# gatedriver.net
KiCad netlist of a schematic drawn in Altium Designer
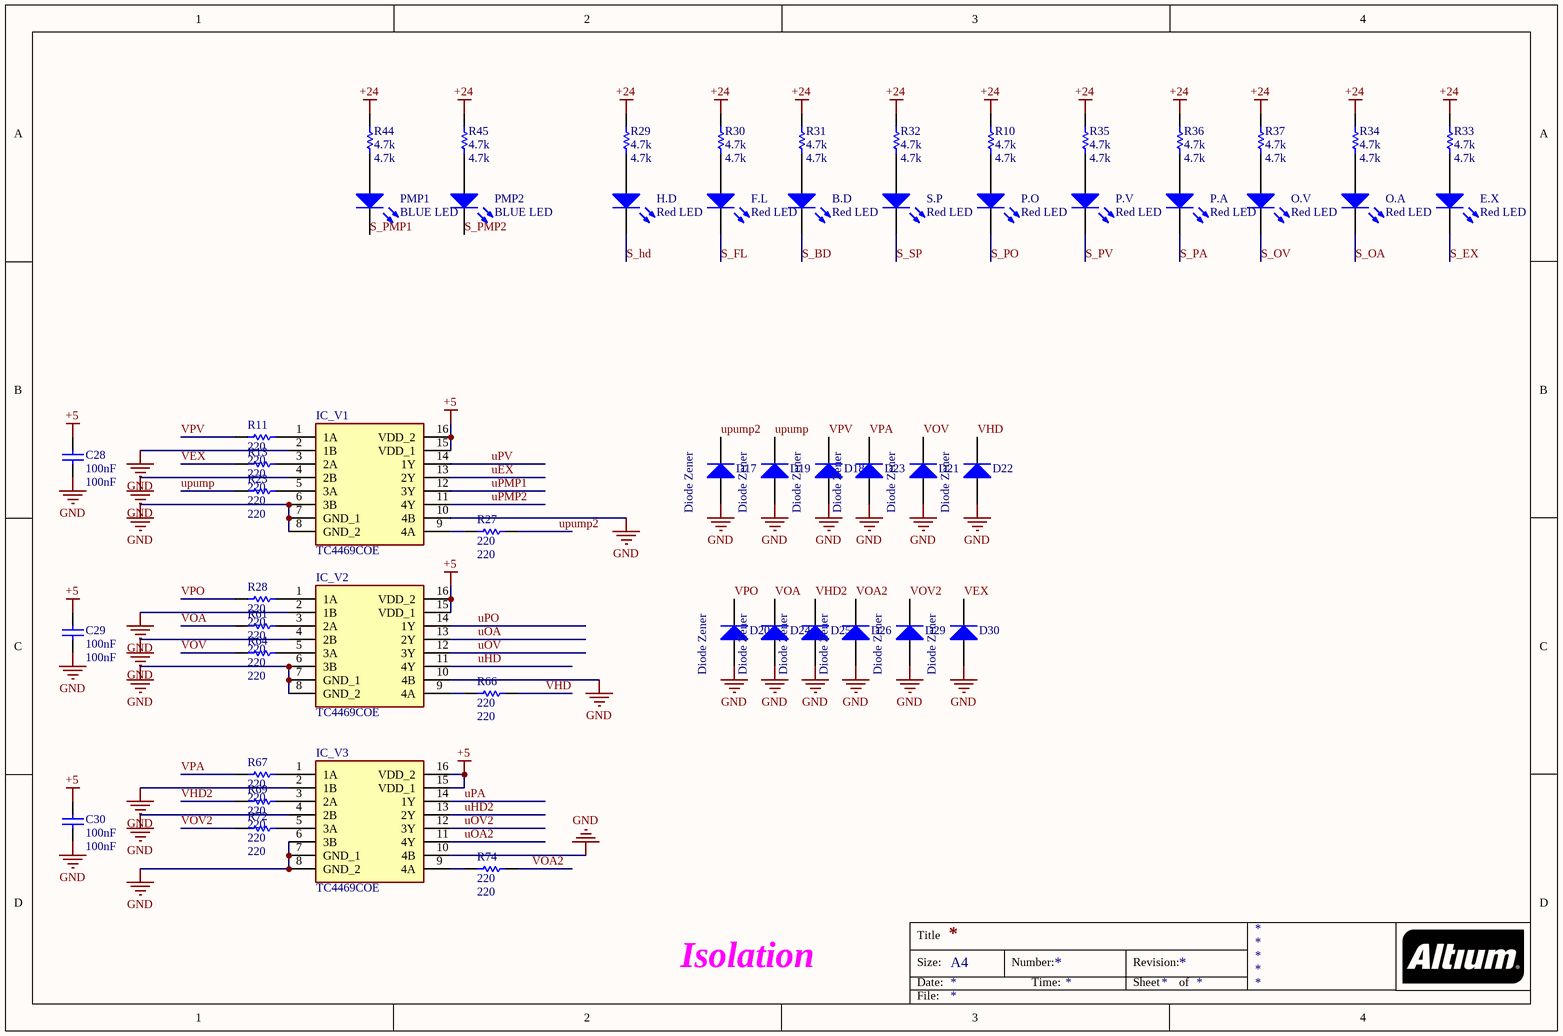
[diagram p0: gatedriver.SchDoc]

(export (version "E")
  (design (tool "Eeschema 10.0.6"))
  (components
    (comp (ref "B.D")
      (value "Red LED")
      (footprint "3518")
      (description "Typical BLUE SiC LED")
      (fields (field (name "PUBLISHER") "Altium Limited"))
      (libsource (lib "Miscellaneous Devices") (part "LED3"))
    )
    (comp (ref "C28")
      (value "100nF")
      (footprint "0805")
      (description "Capacitor")
      (fields
        (field (name "MANUFACTURER") "Generic Components")
        (field (name "ALTIUM_VALUE") "100nF")
        (field (name "PUBLISHER") "Altium Hobart Technology Centre")
      )
      (libsource (lib "Miscellaneous Devices") (part "Cap"))
    )
    (comp (ref "C29")
      (value "100nF")
      (footprint "0805")
      (description "Capacitor")
      (fields
        (field (name "MANUFACTURER") "Generic Components")
        (field (name "ALTIUM_VALUE") "100nF")
        (field (name "PUBLISHER") "Altium Hobart Technology Centre")
      )
      (libsource (lib "Miscellaneous Devices") (part "Cap"))
    )
    (comp (ref "C30")
      (value "100nF")
      (footprint "0805")
      (description "Capacitor")
      (fields
        (field (name "MANUFACTURER") "Generic Components")
        (field (name "ALTIUM_VALUE") "100nF")
        (field (name "PUBLISHER") "Altium Hobart Technology Centre")
      )
      (libsource (lib "Miscellaneous Devices") (part "Cap"))
    )
    (comp (ref "D17")
      (value "Diode Zener")
      (footprint "d1805")
      (description "High Conductance Fast Diode")
      (fields (field (name "PUBLISHER") "Altium Limited"))
      (libsource (lib "Miscellaneous Devices") (part "Diode 1N914"))
    )
    (comp (ref "D18")
      (value "Diode Zener")
      (footprint "d1805")
      (description "High Conductance Fast Diode")
      (fields (field (name "PUBLISHER") "Altium Limited"))
      (libsource (lib "Miscellaneous Devices") (part "Diode 1N914"))
    )
    (comp (ref "D19")
      (value "Diode Zener")
      (footprint "d1805")
      (description "High Conductance Fast Diode")
      (fields (field (name "PUBLISHER") "Altium Limited"))
      (libsource (lib "Miscellaneous Devices") (part "Diode 1N914"))
    )
    (comp (ref "D20")
      (value "Diode Zener")
      (footprint "d1805")
      (description "High Conductance Fast Diode")
      (fields (field (name "PUBLISHER") "Altium Limited"))
      (libsource (lib "Miscellaneous Devices") (part "Diode 1N914"))
    )
    (comp (ref "D21")
      (value "Diode Zener")
      (footprint "d1805")
      (description "High Conductance Fast Diode")
      (fields (field (name "PUBLISHER") "Altium Limited"))
      (libsource (lib "Miscellaneous Devices") (part "Diode 1N914"))
    )
    (comp (ref "D22")
      (value "Diode Zener")
      (footprint "d1805")
      (description "High Conductance Fast Diode")
      (fields (field (name "PUBLISHER") "Altium Limited"))
      (libsource (lib "Miscellaneous Devices") (part "Diode 1N914"))
    )
    (comp (ref "D23")
      (value "Diode Zener")
      (footprint "d1805")
      (description "High Conductance Fast Diode")
      (fields (field (name "PUBLISHER") "Altium Limited"))
      (libsource (lib "Miscellaneous Devices") (part "Diode 1N914"))
    )
    (comp (ref "D24")
      (value "Diode Zener")
      (footprint "d1805")
      (description "High Conductance Fast Diode")
      (fields (field (name "PUBLISHER") "Altium Limited"))
      (libsource (lib "Miscellaneous Devices") (part "Diode 1N914"))
    )
    (comp (ref "D25")
      (value "Diode Zener")
      (footprint "d1805")
      (description "High Conductance Fast Diode")
      (fields (field (name "PUBLISHER") "Altium Limited"))
      (libsource (lib "Miscellaneous Devices") (part "Diode 1N914"))
    )
    (comp (ref "D26")
      (value "Diode Zener")
      (footprint "d1805")
      (description "High Conductance Fast Diode")
      (fields (field (name "PUBLISHER") "Altium Limited"))
      (libsource (lib "Miscellaneous Devices") (part "Diode 1N914"))
    )
    (comp (ref "D29")
      (value "Diode Zener")
      (footprint "d1805")
      (description "High Conductance Fast Diode")
      (fields (field (name "PUBLISHER") "Altium Limited"))
      (libsource (lib "Miscellaneous Devices") (part "Diode 1N914"))
    )
    (comp (ref "D30")
      (value "Diode Zener")
      (footprint "d1805")
      (description "High Conductance Fast Diode")
      (fields (field (name "PUBLISHER") "Altium Limited"))
      (libsource (lib "Miscellaneous Devices") (part "Diode 1N914"))
    )
    (comp (ref "E.X")
      (value "Red LED")
      (footprint "3518")
      (description "Typical BLUE SiC LED")
      (fields (field (name "PUBLISHER") "Altium Limited"))
      (libsource (lib "Miscellaneous Devices") (part "LED3"))
    )
    (comp (ref "F.L")
      (value "Red LED")
      (footprint "3518")
      (description "Typical BLUE SiC LED")
      (fields (field (name "PUBLISHER") "Altium Limited"))
      (libsource (lib "Miscellaneous Devices") (part "LED3"))
    )
    (comp (ref "H.D")
      (value "Red LED")
      (footprint "3518")
      (description "Typical BLUE SiC LED")
      (fields (field (name "PUBLISHER") "Altium Limited"))
      (libsource (lib "Miscellaneous Devices") (part "LED3"))
    )
    (comp (ref "IC_V1")
      (value "TC4469COE")
      (footprint "SamacSys:SOIC127P1034X264-16N")
      (description "Integrated Circuit")
      (fields (field (name "MOUSER PART NUMBER") "579-TC4469COE"))
      (libsource (lib "*") (part "TC4469COE"))
    )
    (comp (ref "IC_V2")
      (value "TC4469COE")
      (footprint "SamacSys:SOIC127P1034X264-16N")
      (description "Integrated Circuit")
      (fields (field (name "MOUSER PART NUMBER") "579-TC4469COE"))
      (libsource (lib "*") (part "TC4469COE"))
    )
    (comp (ref "IC_V3")
      (value "TC4469COE")
      (footprint "SamacSys:SOIC127P1034X264-16N")
      (description "Integrated Circuit")
      (fields (field (name "MOUSER PART NUMBER") "579-TC4469COE"))
      (libsource (lib "*") (part "TC4469COE"))
    )
    (comp (ref "O.A")
      (value "Red LED")
      (footprint "3518")
      (description "Typical BLUE SiC LED")
      (fields (field (name "PUBLISHER") "Altium Limited"))
      (libsource (lib "Miscellaneous Devices") (part "LED3"))
    )
    (comp (ref "O.V")
      (value "Red LED")
      (footprint "3518")
      (description "Typical BLUE SiC LED")
      (fields (field (name "PUBLISHER") "Altium Limited"))
      (libsource (lib "Miscellaneous Devices") (part "LED3"))
    )
    (comp (ref "P.A")
      (value "Red LED")
      (footprint "3518")
      (description "Typical BLUE SiC LED")
      (fields (field (name "PUBLISHER") "Altium Limited"))
      (libsource (lib "Miscellaneous Devices") (part "LED3"))
    )
    (comp (ref "P.O")
      (value "Red LED")
      (footprint "3518")
      (description "Typical BLUE SiC LED")
      (fields (field (name "PUBLISHER") "Altium Limited"))
      (libsource (lib "Miscellaneous Devices") (part "LED3"))
    )
    (comp (ref "P.V")
      (value "Red LED")
      (footprint "3518")
      (description "Typical BLUE SiC LED")
      (fields (field (name "PUBLISHER") "Altium Limited"))
      (libsource (lib "Miscellaneous Devices") (part "LED3"))
    )
    (comp (ref "PMP1")
      (value "BLUE LED")
      (footprint "3518")
      (fields (field (name "PUBLISHER") "Altium Limited"))
      (libsource (lib "Miscellaneous Devices") (part "LED3"))
    )
    (comp (ref "PMP2")
      (value "BLUE LED")
      (footprint "3518")
      (fields (field (name "PUBLISHER") "Altium Limited"))
      (libsource (lib "Miscellaneous Devices") (part "LED3"))
    )
    (comp (ref "R10")
      (value "4.7k")
      (footprint "0805")
      (description "Resistor")
      (fields (field (name "ALTIUM_VALUE") "4.7k") (field (name "PUBLISHER") "Altium Limited"))
      (libsource (lib "Miscellaneous Devices") (part "Res1"))
    )
    (comp (ref "R11")
      (value "220")
      (footprint "0805")
      (description "Resistor")
      (fields (field (name "ALTIUM_VALUE") "220") (field (name "PUBLISHER") "Altium Limited"))
      (libsource (lib "Miscellaneous Devices") (part "Res1"))
    )
    (comp (ref "R13")
      (value "220")
      (footprint "0805")
      (description "Resistor")
      (fields (field (name "ALTIUM_VALUE") "220") (field (name "PUBLISHER") "Altium Limited"))
      (libsource (lib "Miscellaneous Devices") (part "Res1"))
    )
    (comp (ref "R23")
      (value "220")
      (footprint "0805")
      (description "Resistor")
      (fields (field (name "ALTIUM_VALUE") "220") (field (name "PUBLISHER") "Altium Limited"))
      (libsource (lib "Miscellaneous Devices") (part "Res1"))
    )
    (comp (ref "R27")
      (value "220")
      (footprint "0805")
      (description "Resistor")
      (fields (field (name "ALTIUM_VALUE") "220") (field (name "PUBLISHER") "Altium Limited"))
      (libsource (lib "Miscellaneous Devices") (part "Res1"))
    )
    (comp (ref "R28")
      (value "220")
      (footprint "0805")
      (description "Resistor")
      (fields (field (name "ALTIUM_VALUE") "220") (field (name "PUBLISHER") "Altium Limited"))
      (libsource (lib "Miscellaneous Devices") (part "Res1"))
    )
    (comp (ref "R29")
      (value "4.7k")
      (footprint "0805")
      (description "Resistor")
      (fields (field (name "ALTIUM_VALUE") "4.7k") (field (name "PUBLISHER") "Altium Limited"))
      (libsource (lib "Miscellaneous Devices") (part "Res1"))
    )
    (comp (ref "R30")
      (value "4.7k")
      (footprint "0805")
      (description "Resistor")
      (fields (field (name "ALTIUM_VALUE") "4.7k") (field (name "PUBLISHER") "Altium Limited"))
      (libsource (lib "Miscellaneous Devices") (part "Res1"))
    )
    (comp (ref "R31")
      (value "4.7k")
      (footprint "0805")
      (description "Resistor")
      (fields (field (name "ALTIUM_VALUE") "4.7k") (field (name "PUBLISHER") "Altium Limited"))
      (libsource (lib "Miscellaneous Devices") (part "Res1"))
    )
    (comp (ref "R32")
      (value "4.7k")
      (footprint "0805")
      (description "Resistor")
      (fields (field (name "ALTIUM_VALUE") "4.7k") (field (name "PUBLISHER") "Altium Limited"))
      (libsource (lib "Miscellaneous Devices") (part "Res1"))
    )
    (comp (ref "R33")
      (value "4.7k")
      (footprint "0805")
      (description "Resistor")
      (fields (field (name "ALTIUM_VALUE") "4.7k") (field (name "PUBLISHER") "Altium Limited"))
      (libsource (lib "Miscellaneous Devices") (part "Res1"))
    )
    (comp (ref "R34")
      (value "4.7k")
      (footprint "0805")
      (description "Resistor")
      (fields (field (name "ALTIUM_VALUE") "4.7k") (field (name "PUBLISHER") "Altium Limited"))
      (libsource (lib "Miscellaneous Devices") (part "Res1"))
    )
    (comp (ref "R35")
      (value "4.7k")
      (footprint "0805")
      (description "Resistor")
      (fields (field (name "ALTIUM_VALUE") "4.7k") (field (name "PUBLISHER") "Altium Limited"))
      (libsource (lib "Miscellaneous Devices") (part "Res1"))
    )
    (comp (ref "R36")
      (value "4.7k")
      (footprint "0805")
      (description "Resistor")
      (fields (field (name "ALTIUM_VALUE") "4.7k") (field (name "PUBLISHER") "Altium Limited"))
      (libsource (lib "Miscellaneous Devices") (part "Res1"))
    )
    (comp (ref "R37")
      (value "4.7k")
      (footprint "0805")
      (description "Resistor")
      (fields (field (name "ALTIUM_VALUE") "4.7k") (field (name "PUBLISHER") "Altium Limited"))
      (libsource (lib "Miscellaneous Devices") (part "Res1"))
    )
    (comp (ref "R44")
      (value "4.7k")
      (footprint "0805")
      (description "Resistor")
      (fields (field (name "ALTIUM_VALUE") "4.7k") (field (name "PUBLISHER") "Altium Limited"))
      (libsource (lib "Miscellaneous Devices") (part "Res1"))
    )
    (comp (ref "R45")
      (value "4.7k")
      (footprint "0805")
      (description "Resistor")
      (fields (field (name "ALTIUM_VALUE") "4.7k") (field (name "PUBLISHER") "Altium Limited"))
      (libsource (lib "Miscellaneous Devices") (part "Res1"))
    )
    (comp (ref "R61")
      (value "220")
      (footprint "0805")
      (description "Resistor")
      (fields (field (name "ALTIUM_VALUE") "220") (field (name "PUBLISHER") "Altium Limited"))
      (libsource (lib "Miscellaneous Devices") (part "Res1"))
    )
    (comp (ref "R64")
      (value "220")
      (footprint "0805")
      (description "Resistor")
      (fields (field (name "ALTIUM_VALUE") "220") (field (name "PUBLISHER") "Altium Limited"))
      (libsource (lib "Miscellaneous Devices") (part "Res1"))
    )
    (comp (ref "R66")
      (value "220")
      (footprint "0805")
      (description "Resistor")
      (fields (field (name "ALTIUM_VALUE") "220") (field (name "PUBLISHER") "Altium Limited"))
      (libsource (lib "Miscellaneous Devices") (part "Res1"))
    )
    (comp (ref "R67")
      (value "220")
      (footprint "0805")
      (description "Resistor")
      (fields (field (name "ALTIUM_VALUE") "220") (field (name "PUBLISHER") "Altium Limited"))
      (libsource (lib "Miscellaneous Devices") (part "Res1"))
    )
    (comp (ref "R69")
      (value "220")
      (footprint "0805")
      (description "Resistor")
      (fields (field (name "ALTIUM_VALUE") "220") (field (name "PUBLISHER") "Altium Limited"))
      (libsource (lib "Miscellaneous Devices") (part "Res1"))
    )
    (comp (ref "R72")
      (value "220")
      (footprint "0805")
      (description "Resistor")
      (fields (field (name "ALTIUM_VALUE") "220") (field (name "PUBLISHER") "Altium Limited"))
      (libsource (lib "Miscellaneous Devices") (part "Res1"))
    )
    (comp (ref "R74")
      (value "220")
      (footprint "0805")
      (description "Resistor")
      (fields (field (name "ALTIUM_VALUE") "220") (field (name "PUBLISHER") "Altium Limited"))
      (libsource (lib "Miscellaneous Devices") (part "Res1"))
    )
    (comp (ref "S.P")
      (value "Red LED")
      (footprint "3518")
      (description "Typical BLUE SiC LED")
      (fields (field (name "PUBLISHER") "Altium Limited"))
      (libsource (lib "Miscellaneous Devices") (part "LED3"))
    )
  )
  (nets
    (net (code "1") (name "+5") (class "Default")
      (node (ref "C28") (pin "2") (pinfunction "2_2") (pintype "passive"))
      (node (ref "C29") (pin "2") (pinfunction "2_2") (pintype "passive"))
      (node (ref "C30") (pin "2") (pinfunction "2_2") (pintype "passive"))
      (node (ref "IC_V1") (pin "15") (pinfunction "VDD_1_15") (pintype "passive"))
      (node (ref "IC_V1") (pin "16") (pinfunction "VDD_2_16") (pintype "passive"))
      (node (ref "IC_V2") (pin "15") (pinfunction "VDD_1_15") (pintype "passive"))
      (node (ref "IC_V2") (pin "16") (pinfunction "VDD_2_16") (pintype "passive"))
      (node (ref "IC_V3") (pin "15") (pinfunction "VDD_1_15") (pintype "passive"))
      (node (ref "IC_V3") (pin "16") (pinfunction "VDD_2_16") (pintype "passive"))
    )
    (net (code "2") (name "+24") (class "Default")
      (node (ref "R10") (pin "1") (pinfunction "1_1") (pintype "passive"))
      (node (ref "R29") (pin "1") (pinfunction "1_1") (pintype "passive"))
      (node (ref "R30") (pin "1") (pinfunction "1_1") (pintype "passive"))
      (node (ref "R31") (pin "1") (pinfunction "1_1") (pintype "passive"))
      (node (ref "R32") (pin "1") (pinfunction "1_1") (pintype "passive"))
      (node (ref "R33") (pin "1") (pinfunction "1_1") (pintype "passive"))
      (node (ref "R34") (pin "1") (pinfunction "1_1") (pintype "passive"))
      (node (ref "R35") (pin "1") (pinfunction "1_1") (pintype "passive"))
      (node (ref "R36") (pin "1") (pinfunction "1_1") (pintype "passive"))
      (node (ref "R37") (pin "1") (pinfunction "1_1") (pintype "passive"))
      (node (ref "R44") (pin "1") (pinfunction "1_1") (pintype "passive"))
      (node (ref "R45") (pin "1") (pinfunction "1_1") (pintype "passive"))
    )
    (net (code "3") (name "/S_BD") (class "Default")
      (node (ref "B.D") (pin "2") (pinfunction "K_2") (pintype "passive"))
    )
    (net (code "4") (name "/S_EX") (class "Default")
      (node (ref "E.X") (pin "2") (pinfunction "K_2") (pintype "passive"))
    )
    (net (code "5") (name "/S_FL") (class "Default")
      (node (ref "F.L") (pin "2") (pinfunction "K_2") (pintype "passive"))
    )
    (net (code "6") (name "/S_OA") (class "Default")
      (node (ref "O.A") (pin "2") (pinfunction "K_2") (pintype "passive"))
    )
    (net (code "7") (name "/S_OV") (class "Default")
      (node (ref "O.V") (pin "2") (pinfunction "K_2") (pintype "passive"))
    )
    (net (code "8") (name "/S_PA") (class "Default")
      (node (ref "P.A") (pin "2") (pinfunction "K_2") (pintype "passive"))
    )
    (net (code "9") (name "/S_PMP1") (class "Default")
      (node (ref "PMP1") (pin "2") (pinfunction "K_2") (pintype "passive"))
    )
    (net (code "10") (name "/S_PMP2") (class "Default")
      (node (ref "PMP2") (pin "2") (pinfunction "K_2") (pintype "passive"))
    )
    (net (code "11") (name "/S_PO") (class "Default")
      (node (ref "P.O") (pin "2") (pinfunction "K_2") (pintype "passive"))
    )
    (net (code "12") (name "/S_PV") (class "Default")
      (node (ref "P.V") (pin "2") (pinfunction "K_2") (pintype "passive"))
    )
    (net (code "13") (name "/S_SP") (class "Default")
      (node (ref "S.P") (pin "2") (pinfunction "K_2") (pintype "passive"))
    )
    (net (code "14") (name "/S_hd") (class "Default")
      (node (ref "H.D") (pin "2") (pinfunction "K_2") (pintype "passive"))
    )
    (net (code "15") (name "/VEX") (class "Default")
      (node (ref "D30") (pin "2") (pinfunction "K_2") (pintype "passive"))
      (node (ref "R13") (pin "2") (pinfunction "2_2") (pintype "passive"))
    )
    (net (code "16") (name "/VHD") (class "Default")
      (node (ref "D22") (pin "2") (pinfunction "K_2") (pintype "passive"))
      (node (ref "R66") (pin "2") (pinfunction "2_2") (pintype "passive"))
    )
    (net (code "17") (name "/VHD2") (class "Default")
      (node (ref "D25") (pin "2") (pinfunction "K_2") (pintype "passive"))
      (node (ref "R69") (pin "2") (pinfunction "2_2") (pintype "passive"))
    )
    (net (code "18") (name "/VOA") (class "Default")
      (node (ref "D24") (pin "2") (pinfunction "K_2") (pintype "passive"))
      (node (ref "R61") (pin "2") (pinfunction "2_2") (pintype "passive"))
    )
    (net (code "19") (name "/VOA2") (class "Default")
      (node (ref "D26") (pin "2") (pinfunction "K_2") (pintype "passive"))
      (node (ref "R74") (pin "2") (pinfunction "2_2") (pintype "passive"))
    )
    (net (code "20") (name "/VOV") (class "Default")
      (node (ref "D21") (pin "2") (pinfunction "K_2") (pintype "passive"))
      (node (ref "R64") (pin "2") (pinfunction "2_2") (pintype "passive"))
    )
    (net (code "21") (name "/VOV2") (class "Default")
      (node (ref "D29") (pin "2") (pinfunction "K_2") (pintype "passive"))
      (node (ref "R72") (pin "2") (pinfunction "2_2") (pintype "passive"))
    )
    (net (code "22") (name "/VPA") (class "Default")
      (node (ref "D23") (pin "2") (pinfunction "K_2") (pintype "passive"))
      (node (ref "R67") (pin "1") (pinfunction "1_1") (pintype "passive"))
    )
    (net (code "23") (name "/VPO") (class "Default")
      (node (ref "D20") (pin "2") (pinfunction "K_2") (pintype "passive"))
      (node (ref "R28") (pin "1") (pinfunction "1_1") (pintype "passive"))
    )
    (net (code "24") (name "/VPV") (class "Default")
      (node (ref "D18") (pin "2") (pinfunction "K_2") (pintype "passive"))
      (node (ref "R11") (pin "1") (pinfunction "1_1") (pintype "passive"))
    )
    (net (code "25") (name "/uEX") (class "Default")
      (node (ref "IC_V1") (pin "13") (pinfunction "2Y_13") (pintype "passive"))
    )
    (net (code "26") (name "/uHD") (class "Default")
      (node (ref "IC_V2") (pin "11") (pinfunction "4Y_11") (pintype "passive"))
    )
    (net (code "27") (name "/uHD2") (class "Default")
      (node (ref "IC_V3") (pin "13") (pinfunction "2Y_13") (pintype "passive"))
    )
    (net (code "28") (name "/uOA") (class "Default")
      (node (ref "IC_V2") (pin "13") (pinfunction "2Y_13") (pintype "passive"))
    )
    (net (code "29") (name "/uOA2") (class "Default")
      (node (ref "IC_V3") (pin "11") (pinfunction "4Y_11") (pintype "passive"))
    )
    (net (code "30") (name "/uOV") (class "Default")
      (node (ref "IC_V2") (pin "12") (pinfunction "3Y_12") (pintype "passive"))
    )
    (net (code "31") (name "/uOV2") (class "Default")
      (node (ref "IC_V3") (pin "12") (pinfunction "3Y_12") (pintype "passive"))
    )
    (net (code "32") (name "/uPA") (class "Default")
      (node (ref "IC_V3") (pin "14") (pinfunction "1Y_14") (pintype "passive"))
    )
    (net (code "33") (name "/uPMP1") (class "Default")
      (node (ref "IC_V1") (pin "12") (pinfunction "3Y_12") (pintype "passive"))
    )
    (net (code "34") (name "/uPMP2") (class "Default")
      (node (ref "IC_V1") (pin "11") (pinfunction "4Y_11") (pintype "passive"))
    )
    (net (code "35") (name "/uPO") (class "Default")
      (node (ref "IC_V2") (pin "14") (pinfunction "1Y_14") (pintype "passive"))
    )
    (net (code "36") (name "/uPV") (class "Default")
      (node (ref "IC_V1") (pin "14") (pinfunction "1Y_14") (pintype "passive"))
    )
    (net (code "37") (name "/upump") (class "Default")
      (node (ref "D19") (pin "2") (pinfunction "K_2") (pintype "passive"))
      (node (ref "R23") (pin "2") (pinfunction "2_2") (pintype "passive"))
    )
    (net (code "38") (name "/upump2") (class "Default")
      (node (ref "D17") (pin "2") (pinfunction "K_2") (pintype "passive"))
      (node (ref "R27") (pin "2") (pinfunction "2_2") (pintype "passive"))
    )
    (net (code "39") (name "GND") (class "Default")
      (node (ref "C28") (pin "1") (pinfunction "1_1") (pintype "passive"))
      (node (ref "C29") (pin "1") (pinfunction "1_1") (pintype "passive"))
      (node (ref "C30") (pin "1") (pinfunction "1_1") (pintype "passive"))
      (node (ref "D17") (pin "1") (pinfunction "A_1") (pintype "passive"))
      (node (ref "D18") (pin "1") (pinfunction "A_1") (pintype "passive"))
      (node (ref "D19") (pin "1") (pinfunction "A_1") (pintype "passive"))
      (node (ref "D20") (pin "1") (pinfunction "A_1") (pintype "passive"))
      (node (ref "D21") (pin "1") (pinfunction "A_1") (pintype "passive"))
      (node (ref "D22") (pin "1") (pinfunction "A_1") (pintype "passive"))
      (node (ref "D23") (pin "1") (pinfunction "A_1") (pintype "passive"))
      (node (ref "D24") (pin "1") (pinfunction "A_1") (pintype "passive"))
      (node (ref "D25") (pin "1") (pinfunction "A_1") (pintype "passive"))
      (node (ref "D26") (pin "1") (pinfunction "A_1") (pintype "passive"))
      (node (ref "D29") (pin "1") (pinfunction "A_1") (pintype "passive"))
      (node (ref "D30") (pin "1") (pinfunction "A_1") (pintype "passive"))
      (node (ref "IC_V1") (pin "10") (pinfunction "4B_10") (pintype "passive"))
      (node (ref "IC_V1") (pin "2") (pinfunction "1B_2") (pintype "passive"))
      (node (ref "IC_V1") (pin "4") (pinfunction "2B_4") (pintype "passive"))
      (node (ref "IC_V1") (pin "6") (pinfunction "3B_6") (pintype "passive"))
      (node (ref "IC_V1") (pin "7") (pinfunction "GND_1_7") (pintype "passive"))
      (node (ref "IC_V1") (pin "8") (pinfunction "GND_2_8") (pintype "passive"))
      (node (ref "IC_V2") (pin "10") (pinfunction "4B_10") (pintype "passive"))
      (node (ref "IC_V2") (pin "2") (pinfunction "1B_2") (pintype "passive"))
      (node (ref "IC_V2") (pin "4") (pinfunction "2B_4") (pintype "passive"))
      (node (ref "IC_V2") (pin "6") (pinfunction "3B_6") (pintype "passive"))
      (node (ref "IC_V2") (pin "7") (pinfunction "GND_1_7") (pintype "passive"))
      (node (ref "IC_V2") (pin "8") (pinfunction "GND_2_8") (pintype "passive"))
      (node (ref "IC_V3") (pin "10") (pinfunction "4B_10") (pintype "passive"))
      (node (ref "IC_V3") (pin "2") (pinfunction "1B_2") (pintype "passive"))
      (node (ref "IC_V3") (pin "4") (pinfunction "2B_4") (pintype "passive"))
      (node (ref "IC_V3") (pin "6") (pinfunction "3B_6") (pintype "passive"))
      (node (ref "IC_V3") (pin "7") (pinfunction "GND_1_7") (pintype "passive"))
      (node (ref "IC_V3") (pin "8") (pinfunction "GND_2_8") (pintype "passive"))
    )
    (net (code "40") (name "Net-(B.D-A)") (class "Default")
      (node (ref "B.D") (pin "1") (pinfunction "A_1") (pintype "passive"))
      (node (ref "R31") (pin "2") (pinfunction "2_2") (pintype "passive"))
    )
    (net (code "41") (name "Net-(E.X-A)") (class "Default")
      (node (ref "E.X") (pin "1") (pinfunction "A_1") (pintype "passive"))
      (node (ref "R33") (pin "2") (pinfunction "2_2") (pintype "passive"))
    )
    (net (code "42") (name "Net-(F.L-A)") (class "Default")
      (node (ref "F.L") (pin "1") (pinfunction "A_1") (pintype "passive"))
      (node (ref "R30") (pin "2") (pinfunction "2_2") (pintype "passive"))
    )
    (net (code "43") (name "Net-(H.D-A)") (class "Default")
      (node (ref "H.D") (pin "1") (pinfunction "A_1") (pintype "passive"))
      (node (ref "R29") (pin "2") (pinfunction "2_2") (pintype "passive"))
    )
    (net (code "44") (name "Net-(IC_V1-1A)") (class "Default")
      (node (ref "IC_V1") (pin "1") (pinfunction "1A_1") (pintype "passive"))
      (node (ref "R11") (pin "2") (pinfunction "2_2") (pintype "passive"))
    )
    (net (code "45") (name "Net-(IC_V1-2A)") (class "Default")
      (node (ref "IC_V1") (pin "3") (pinfunction "2A_3") (pintype "passive"))
      (node (ref "R13") (pin "1") (pinfunction "1_1") (pintype "passive"))
    )
    (net (code "46") (name "Net-(IC_V1-3A)") (class "Default")
      (node (ref "IC_V1") (pin "5") (pinfunction "3A_5") (pintype "passive"))
      (node (ref "R23") (pin "1") (pinfunction "1_1") (pintype "passive"))
    )
    (net (code "47") (name "Net-(IC_V1-4A)") (class "Default")
      (node (ref "IC_V1") (pin "9") (pinfunction "4A_9") (pintype "passive"))
      (node (ref "R27") (pin "1") (pinfunction "1_1") (pintype "passive"))
    )
    (net (code "48") (name "Net-(IC_V2-1A)") (class "Default")
      (node (ref "IC_V2") (pin "1") (pinfunction "1A_1") (pintype "passive"))
      (node (ref "R28") (pin "2") (pinfunction "2_2") (pintype "passive"))
    )
    (net (code "49") (name "Net-(IC_V2-2A)") (class "Default")
      (node (ref "IC_V2") (pin "3") (pinfunction "2A_3") (pintype "passive"))
      (node (ref "R61") (pin "1") (pinfunction "1_1") (pintype "passive"))
    )
    (net (code "50") (name "Net-(IC_V2-3A)") (class "Default")
      (node (ref "IC_V2") (pin "5") (pinfunction "3A_5") (pintype "passive"))
      (node (ref "R64") (pin "1") (pinfunction "1_1") (pintype "passive"))
    )
    (net (code "51") (name "Net-(IC_V2-4A)") (class "Default")
      (node (ref "IC_V2") (pin "9") (pinfunction "4A_9") (pintype "passive"))
      (node (ref "R66") (pin "1") (pinfunction "1_1") (pintype "passive"))
    )
    (net (code "52") (name "Net-(IC_V3-1A)") (class "Default")
      (node (ref "IC_V3") (pin "1") (pinfunction "1A_1") (pintype "passive"))
      (node (ref "R67") (pin "2") (pinfunction "2_2") (pintype "passive"))
    )
    (net (code "53") (name "Net-(IC_V3-2A)") (class "Default")
      (node (ref "IC_V3") (pin "3") (pinfunction "2A_3") (pintype "passive"))
      (node (ref "R69") (pin "1") (pinfunction "1_1") (pintype "passive"))
    )
    (net (code "54") (name "Net-(IC_V3-3A)") (class "Default")
      (node (ref "IC_V3") (pin "5") (pinfunction "3A_5") (pintype "passive"))
      (node (ref "R72") (pin "1") (pinfunction "1_1") (pintype "passive"))
    )
    (net (code "55") (name "Net-(IC_V3-4A)") (class "Default")
      (node (ref "IC_V3") (pin "9") (pinfunction "4A_9") (pintype "passive"))
      (node (ref "R74") (pin "1") (pinfunction "1_1") (pintype "passive"))
    )
    (net (code "56") (name "Net-(O.A-A)") (class "Default")
      (node (ref "O.A") (pin "1") (pinfunction "A_1") (pintype "passive"))
      (node (ref "R34") (pin "2") (pinfunction "2_2") (pintype "passive"))
    )
    (net (code "57") (name "Net-(O.V-A)") (class "Default")
      (node (ref "O.V") (pin "1") (pinfunction "A_1") (pintype "passive"))
      (node (ref "R37") (pin "2") (pinfunction "2_2") (pintype "passive"))
    )
    (net (code "58") (name "Net-(P.A-A)") (class "Default")
      (node (ref "P.A") (pin "1") (pinfunction "A_1") (pintype "passive"))
      (node (ref "R36") (pin "2") (pinfunction "2_2") (pintype "passive"))
    )
    (net (code "59") (name "Net-(P.O-A)") (class "Default")
      (node (ref "P.O") (pin "1") (pinfunction "A_1") (pintype "passive"))
      (node (ref "R10") (pin "2") (pinfunction "2_2") (pintype "passive"))
    )
    (net (code "60") (name "Net-(P.V-A)") (class "Default")
      (node (ref "P.V") (pin "1") (pinfunction "A_1") (pintype "passive"))
      (node (ref "R35") (pin "2") (pinfunction "2_2") (pintype "passive"))
    )
    (net (code "61") (name "Net-(PMP1-A)") (class "Default")
      (node (ref "PMP1") (pin "1") (pinfunction "A_1") (pintype "passive"))
      (node (ref "R44") (pin "2") (pinfunction "2_2") (pintype "passive"))
    )
    (net (code "62") (name "Net-(PMP2-A)") (class "Default")
      (node (ref "PMP2") (pin "1") (pinfunction "A_1") (pintype "passive"))
      (node (ref "R45") (pin "2") (pinfunction "2_2") (pintype "passive"))
    )
    (net (code "63") (name "Net-(S.P-A)") (class "Default")
      (node (ref "R32") (pin "2") (pinfunction "2_2") (pintype "passive"))
      (node (ref "S.P") (pin "1") (pinfunction "A_1") (pintype "passive"))
    )
  )
)
